# design.net
KiCad netlist of a schematic drawn in Altium Designer
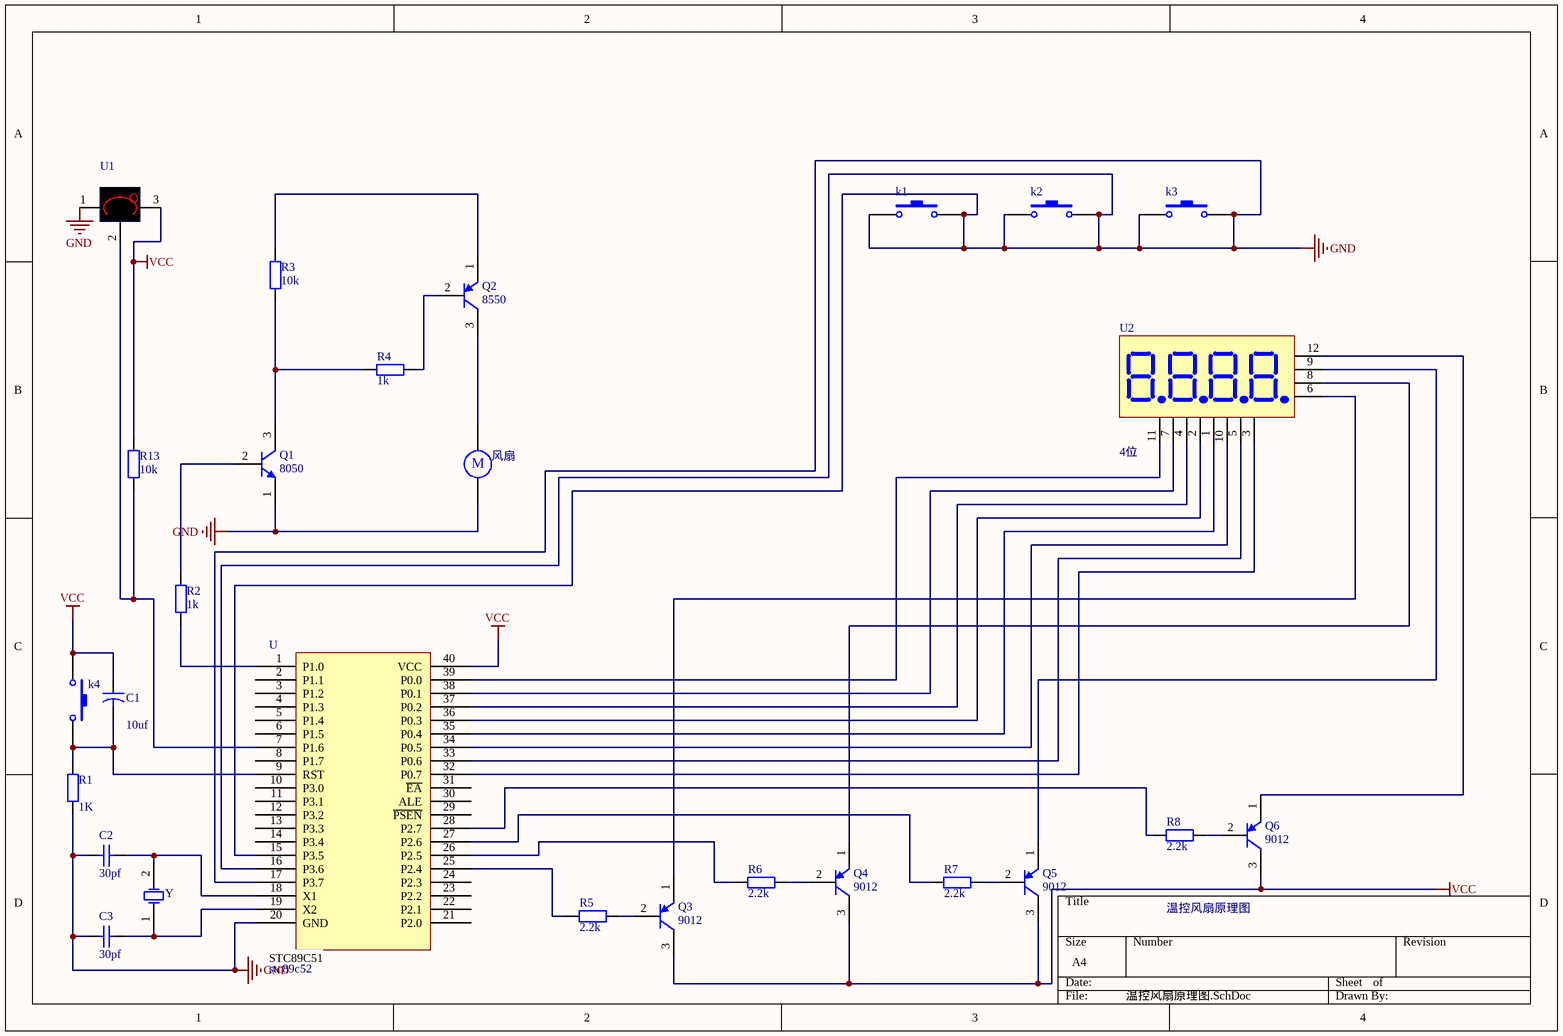
[diagram p0: 温控风扇原理图.SchDoc]

(export (version "E")
  (design (tool "Eeschema 10.0.6"))
  (components
    (comp (ref "C1")
      (value "10uf")
      (footprint "CAPR5-4X5")
      (description "Capacitor")
      (fields (field (name "Comment") "Cap2") (field (name "PUBLISHER") "Altium Limited"))
      (libsource (lib "Miscellaneous Devices") (part "Cap2"))
    )
    (comp (ref "C2")
      (value "30pf")
      (footprint "1206_C")
      (description "1206贴片电容")
      (libsource (lib "02 Miscellaneous_Devices_ZSF_Library") (part "Cap_1206"))
    )
    (comp (ref "C3")
      (value "30pf")
      (footprint "1206_C")
      (description "1206贴片电容")
      (libsource (lib "02 Miscellaneous_Devices_ZSF_Library") (part "Cap_1206"))
    )
    (comp (ref "k1")
      (value "Tactile Switch")
      (footprint "BUTTON_6*6")
      (description "Tactile Switch触觉开关")
      (fields (field (name "PUBLISHER") "Altium Limited"))
      (libsource (lib "02 Miscellaneous_Devices_ZSF_Library") (part "SW-PB"))
    )
    (comp (ref "k2")
      (value "Tactile Switch")
      (footprint "BUTTON_6*6")
      (description "Tactile Switch触觉开关")
      (fields (field (name "PUBLISHER") "Altium Limited"))
      (libsource (lib "02 Miscellaneous_Devices_ZSF_Library") (part "SW-PB"))
    )
    (comp (ref "k3")
      (value "Tactile Switch")
      (footprint "BUTTON_6*6")
      (description "Tactile Switch触觉开关")
      (fields (field (name "PUBLISHER") "Altium Limited"))
      (libsource (lib "02 Miscellaneous_Devices_ZSF_Library") (part "SW-PB"))
    )
    (comp (ref "k4")
      (value "Tactile Switch")
      (footprint "BUTTON_6*6")
      (description "Tactile Switch触觉开关")
      (fields (field (name "PUBLISHER") "Altium Limited"))
      (libsource (lib "02 Miscellaneous_Devices_ZSF_Library") (part "SW-PB"))
    )
    (comp (ref "Q1")
      (value "8050")
      (footprint "TO-92(TO-92-3)")
      (description "NPN型小功率三极管")
      (libsource (lib "02 Miscellaneous_Devices_ZSF_Library") (part "8050_TO-92"))
    )
    (comp (ref "Q2")
      (value "8550")
      (footprint "TO-92(TO-92-3)")
      (description "PNP型小功率三极管")
      (libsource (lib "02 Miscellaneous_Devices_ZSF_Library") (part "8550_TO-92"))
    )
    (comp (ref "Q3")
      (value "9012")
      (footprint "TO-92(TO-92-3)")
      (description "PNP型小功率三极管")
      (libsource (lib "02 Miscellaneous_Devices_ZSF_Library") (part "9012_TO-92"))
    )
    (comp (ref "Q4")
      (value "9012")
      (footprint "TO-92(TO-92-3)")
      (description "PNP型小功率三极管")
      (libsource (lib "02 Miscellaneous_Devices_ZSF_Library") (part "9012_TO-92"))
    )
    (comp (ref "Q5")
      (value "9012")
      (footprint "TO-92(TO-92-3)")
      (description "PNP型小功率三极管")
      (libsource (lib "02 Miscellaneous_Devices_ZSF_Library") (part "9012_TO-92"))
    )
    (comp (ref "Q6")
      (value "9012")
      (footprint "TO-92(TO-92-3)")
      (description "PNP型小功率三极管")
      (libsource (lib "02 Miscellaneous_Devices_ZSF_Library") (part "9012_TO-92"))
    )
    (comp (ref "R1")
      (value "1K")
      (footprint "AXIAL-0.4")
      (description "Resistor")
      (fields (field (name "Comment") "Res2") (field (name "PUBLISHER") "Altium Limited"))
      (libsource (lib "Miscellaneous Devices") (part "Res2"))
    )
    (comp (ref "R2")
      (value "1k")
      (footprint "AXIAL-0.6-R")
      (description "Resistor 直插电阻 1W")
      (fields (field (name "PUBLISHER") "Altium Limited"))
      (libsource (lib "02 Miscellaneous_Devices_ZSF_Library") (part "Res2_1W"))
    )
    (comp (ref "R3")
      (value "10k")
      (footprint "AXIAL-0.6-R")
      (description "Resistor 直插电阻 1W")
      (fields (field (name "PUBLISHER") "Altium Limited"))
      (libsource (lib "02 Miscellaneous_Devices_ZSF_Library") (part "Res2_1W"))
    )
    (comp (ref "R4")
      (value "1k")
      (footprint "AXIAL-0.6-R")
      (description "Resistor 直插电阻 1W")
      (fields (field (name "PUBLISHER") "Altium Limited"))
      (libsource (lib "") (part "Res2_1W_1"))
    )
    (comp (ref "R5")
      (value "2.2k")
      (footprint "AXIAL-0.8-R")
      (description "Resistor 直插电阻 2W")
      (fields (field (name "PUBLISHER") "Altium Limited"))
      (libsource (lib "02 Miscellaneous_Devices_ZSF_Library") (part "Res2_2W"))
    )
    (comp (ref "R6")
      (value "2.2k")
      (footprint "AXIAL-0.8-R")
      (description "Resistor 直插电阻 2W")
      (fields (field (name "PUBLISHER") "Altium Limited"))
      (libsource (lib "02 Miscellaneous_Devices_ZSF_Library") (part "Res2_2W"))
    )
    (comp (ref "R7")
      (value "2.2k")
      (footprint "AXIAL-0.8-R")
      (description "Resistor 直插电阻 2W")
      (fields (field (name "PUBLISHER") "Altium Limited"))
      (libsource (lib "02 Miscellaneous_Devices_ZSF_Library") (part "Res2_2W"))
    )
    (comp (ref "R8")
      (value "2.2k")
      (footprint "AXIAL-0.8-R")
      (description "Resistor 直插电阻 2W")
      (fields (field (name "PUBLISHER") "Altium Limited"))
      (libsource (lib "02 Miscellaneous_Devices_ZSF_Library") (part "Res2_2W"))
    )
    (comp (ref "R13")
      (value "10k")
      (footprint "AXIAL-0.6-R")
      (description "Resistor 直插电阻 1W")
      (fields (field (name "PUBLISHER") "Altium Limited"))
      (libsource (lib "02 Miscellaneous_Devices_ZSF_Library") (part "Res2_1W"))
    )
    (comp (ref "U")
      (value "stc89c52")
      (footprint "stc89c52:stc89c52")
      (libsource (lib "stc89c52") (part "stc89c52"))
    )
    (comp (ref "U1")
      (value "DSB18B20")
      (footprint "BCY-W3/E4")
      (description "Temperature Sensor")
      (libsource (lib "03-EButterflyIntegratedLibrary") (part "DSB18B20"))
    )
    (comp (ref "U2")
      (value "4位")
      (footprint "SEG4_3641")
      (description "4位一体共阳数码管 0.36英寸30mm*14mm*7.2mm")
      (libsource (lib "02 Miscellaneous_Devices_ZSF_Library") (part "4位-共阳"))
    )
    (comp (ref "Y")
      (value "XTAL")
      (footprint "R38")
      (description "Crystal Oscillator")
      (fields (field (name "PUBLISHER") "Altium Limited"))
      (libsource (lib "Miscellaneous Devices") (part "XTAL"))
    )
    (comp (ref "风扇")
      (value "Motor")
      (footprint "RB5-10.5")
      (description "Motor, General Kind")
      (fields (field (name "PUBLISHER") "Altium Limited"))
      (libsource (lib "Miscellaneous Devices") (part "Motor"))
    )
  )
  (nets
    (net (code "1") (name "GND") (class "Default")
      (node (ref "C2") (pin "1") (pinfunction "1_1") (pintype "passive"))
      (node (ref "C3") (pin "1") (pinfunction "1_1") (pintype "passive"))
      (node (ref "Q1") (pin "1") (pinfunction "E_1") (pintype "passive"))
      (node (ref "R1") (pin "1") (pinfunction "1_1") (pintype "passive"))
      (node (ref "U") (pin "15") (pinfunction "P3.5_15") (pintype "passive"))
      (node (ref "U") (pin "16") (pinfunction "P3.6_16") (pintype "passive"))
      (node (ref "U") (pin "17") (pinfunction "P3.7_17") (pintype "passive"))
      (node (ref "U") (pin "20") (pinfunction "GND_20") (pintype "passive"))
      (node (ref "U1") (pin "1") (pinfunction "GND_1") (pintype "passive"))
      (node (ref "k1") (pin "1") (pinfunction "1_1") (pintype "passive"))
      (node (ref "k1") (pin "2") (pinfunction "2_2") (pintype "passive"))
      (node (ref "k2") (pin "1") (pinfunction "1_1") (pintype "passive"))
      (node (ref "k2") (pin "2") (pinfunction "2_2") (pintype "passive"))
      (node (ref "k3") (pin "1") (pinfunction "1_1") (pintype "passive"))
      (node (ref "k3") (pin "2") (pinfunction "2_2") (pintype "passive"))
      (node (ref "风扇") (pin "2") (pinfunction "2_2") (pintype "passive"))
    )
    (net (code "2") (name "Net-(Q1-B)") (class "Default")
      (node (ref "Q1") (pin "2") (pinfunction "B_2") (pintype "passive"))
      (node (ref "R2") (pin "2") (pinfunction "2_2") (pintype "passive"))
    )
    (net (code "3") (name "Net-(Q1-C)") (class "Default")
      (node (ref "Q1") (pin "3") (pinfunction "C_3") (pintype "passive"))
      (node (ref "R3") (pin "1") (pinfunction "1_1") (pintype "passive"))
      (node (ref "R4") (pin "1") (pinfunction "1_1") (pintype "passive"))
    )
    (net (code "4") (name "Net-(Q2-B)") (class "Default")
      (node (ref "Q2") (pin "2") (pinfunction "B_2") (pintype "passive"))
      (node (ref "R4") (pin "2") (pinfunction "2_2") (pintype "passive"))
    )
    (net (code "5") (name "Net-(Q2-C)") (class "Default")
      (node (ref "Q2") (pin "3") (pinfunction "C_3") (pintype "passive"))
      (node (ref "风扇") (pin "1") (pinfunction "1_1") (pintype "passive"))
    )
    (net (code "6") (name "Net-(Q2-E)") (class "Default")
      (node (ref "Q2") (pin "1") (pinfunction "E_1") (pintype "passive"))
      (node (ref "R3") (pin "2") (pinfunction "2_2") (pintype "passive"))
    )
    (net (code "7") (name "Net-(Q3-B)") (class "Default")
      (node (ref "Q3") (pin "2") (pinfunction "B_2") (pintype "passive"))
      (node (ref "R5") (pin "2") (pinfunction "2_2") (pintype "passive"))
    )
    (net (code "8") (name "Net-(Q3-E)") (class "Default")
      (node (ref "Q3") (pin "1") (pinfunction "E_1") (pintype "passive"))
      (node (ref "U2") (pin "6") (pinfunction "h1_6") (pintype "passive"))
    )
    (net (code "9") (name "Net-(Q4-B)") (class "Default")
      (node (ref "Q4") (pin "2") (pinfunction "B_2") (pintype "passive"))
      (node (ref "R6") (pin "2") (pinfunction "2_2") (pintype "passive"))
    )
    (net (code "10") (name "Net-(Q4-E)") (class "Default")
      (node (ref "Q4") (pin "1") (pinfunction "E_1") (pintype "passive"))
      (node (ref "U2") (pin "8") (pinfunction "h2_8") (pintype "passive"))
    )
    (net (code "11") (name "Net-(Q5-B)") (class "Default")
      (node (ref "Q5") (pin "2") (pinfunction "B_2") (pintype "passive"))
      (node (ref "R7") (pin "2") (pinfunction "2_2") (pintype "passive"))
    )
    (net (code "12") (name "Net-(Q5-E)") (class "Default")
      (node (ref "Q5") (pin "1") (pinfunction "E_1") (pintype "passive"))
      (node (ref "U2") (pin "9") (pinfunction "h3_9") (pintype "passive"))
    )
    (net (code "13") (name "Net-(Q6-B)") (class "Default")
      (node (ref "Q6") (pin "2") (pinfunction "B_2") (pintype "passive"))
      (node (ref "R8") (pin "2") (pinfunction "2_2") (pintype "passive"))
    )
    (net (code "14") (name "Net-(Q6-E)") (class "Default")
      (node (ref "Q6") (pin "1") (pinfunction "E_1") (pintype "passive"))
      (node (ref "U2") (pin "12") (pinfunction "h4_12") (pintype "passive"))
    )
    (net (code "15") (name "Net-(U-P0.0)") (class "Default")
      (node (ref "U") (pin "39") (pinfunction "P0.0_39") (pintype "passive"))
      (node (ref "U2") (pin "11") (pinfunction "a_11") (pintype "passive"))
    )
    (net (code "16") (name "Net-(U-P0.1)") (class "Default")
      (node (ref "U") (pin "38") (pinfunction "P0.1_38") (pintype "passive"))
      (node (ref "U2") (pin "7") (pinfunction "b_7") (pintype "passive"))
    )
    (net (code "17") (name "Net-(U-P0.2)") (class "Default")
      (node (ref "U") (pin "37") (pinfunction "P0.2_37") (pintype "passive"))
      (node (ref "U2") (pin "4") (pinfunction "c_4") (pintype "passive"))
    )
    (net (code "18") (name "Net-(U-P0.3)") (class "Default")
      (node (ref "U") (pin "36") (pinfunction "P0.3_36") (pintype "passive"))
      (node (ref "U2") (pin "2") (pinfunction "d_2") (pintype "passive"))
    )
    (net (code "19") (name "Net-(U-P0.4)") (class "Default")
      (node (ref "U") (pin "35") (pinfunction "P0.4_35") (pintype "passive"))
      (node (ref "U2") (pin "1") (pinfunction "e_1") (pintype "passive"))
    )
    (net (code "20") (name "Net-(U-P0.5)") (class "Default")
      (node (ref "U") (pin "34") (pinfunction "P0.5_34") (pintype "passive"))
      (node (ref "U2") (pin "10") (pinfunction "f_10") (pintype "passive"))
    )
    (net (code "21") (name "Net-(U-P0.6)") (class "Default")
      (node (ref "U") (pin "33") (pinfunction "P0.6_33") (pintype "passive"))
      (node (ref "U2") (pin "5") (pinfunction "g_5") (pintype "passive"))
    )
    (net (code "22") (name "Net-(U-P0.7)") (class "Default")
      (node (ref "U") (pin "32") (pinfunction "P0.7_32") (pintype "passive"))
      (node (ref "U2") (pin "3") (pinfunction "dp_3") (pintype "passive"))
    )
    (net (code "23") (name "Net-(U-P1.0)") (class "Default")
      (node (ref "R2") (pin "1") (pinfunction "1_1") (pintype "passive"))
      (node (ref "U") (pin "1") (pinfunction "P1.0_1") (pintype "passive"))
    )
    (net (code "24") (name "Net-(U-P1.6)") (class "Default")
      (node (ref "R13") (pin "1") (pinfunction "1_1") (pintype "passive"))
      (node (ref "U") (pin "7") (pinfunction "P1.6_7") (pintype "passive"))
      (node (ref "U1") (pin "2") (pinfunction "DATA_2") (pintype "passive"))
    )
    (net (code "25") (name "Net-(U-P2.4)") (class "Default")
      (node (ref "R5") (pin "1") (pinfunction "1_1") (pintype "passive"))
      (node (ref "U") (pin "25") (pinfunction "P2.4_25") (pintype "passive"))
    )
    (net (code "26") (name "Net-(U-P2.5)") (class "Default")
      (node (ref "R6") (pin "1") (pinfunction "1_1") (pintype "passive"))
      (node (ref "U") (pin "26") (pinfunction "P2.5_26") (pintype "passive"))
    )
    (net (code "27") (name "Net-(U-P2.6)") (class "Default")
      (node (ref "R7") (pin "1") (pinfunction "1_1") (pintype "passive"))
      (node (ref "U") (pin "27") (pinfunction "P2.6_27") (pintype "passive"))
    )
    (net (code "28") (name "Net-(U-P2.7)") (class "Default")
      (node (ref "R8") (pin "1") (pinfunction "1_1") (pintype "passive"))
      (node (ref "U") (pin "28") (pinfunction "P2.7_28") (pintype "passive"))
    )
    (net (code "29") (name "Net-(U-RST)") (class "Default")
      (node (ref "C1") (pin "2") (pinfunction "2_2") (pintype "passive"))
      (node (ref "R1") (pin "2") (pinfunction "2_2") (pintype "passive"))
      (node (ref "U") (pin "9") (pinfunction "RST_9") (pintype "passive"))
      (node (ref "k4") (pin "2") (pinfunction "2_2") (pintype "passive"))
    )
    (net (code "30") (name "Net-(U-X1)") (class "Default")
      (node (ref "C2") (pin "2") (pinfunction "2_2") (pintype "passive"))
      (node (ref "U") (pin "18") (pinfunction "X1_18") (pintype "passive"))
      (node (ref "Y") (pin "2") (pinfunction "OSC2_2") (pintype "passive"))
    )
    (net (code "31") (name "Net-(U-X2)") (class "Default")
      (node (ref "C3") (pin "2") (pinfunction "2_2") (pintype "passive"))
      (node (ref "U") (pin "19") (pinfunction "X2_19") (pintype "passive"))
      (node (ref "Y") (pin "1") (pinfunction "OSC1_1") (pintype "passive"))
    )
    (net (code "32") (name "VCC") (class "Default")
      (node (ref "C1") (pin "1") (pinfunction "1_1") (pintype "passive"))
      (node (ref "Q3") (pin "3") (pinfunction "C_3") (pintype "passive"))
      (node (ref "Q4") (pin "3") (pinfunction "C_3") (pintype "passive"))
      (node (ref "Q5") (pin "3") (pinfunction "C_3") (pintype "passive"))
      (node (ref "Q6") (pin "3") (pinfunction "C_3") (pintype "passive"))
      (node (ref "R13") (pin "2") (pinfunction "2_2") (pintype "passive"))
      (node (ref "U") (pin "40") (pinfunction "VCC_40") (pintype "passive"))
      (node (ref "U1") (pin "3") (pinfunction "VDD_3") (pintype "passive"))
      (node (ref "k4") (pin "1") (pinfunction "1_1") (pintype "passive"))
    )
    (net (code "33") (name "unconnected-(U-ALE-Pad30)") (class "Default")
      (node (ref "U") (pin "30") (pinfunction "ALE_30") (pintype "passive"))
    )
    (net (code "34") (name "unconnected-(U-P1.1-Pad2)") (class "Default")
      (node (ref "U") (pin "2") (pinfunction "P1.1_2") (pintype "passive"))
    )
    (net (code "35") (name "unconnected-(U-P1.2-Pad3)") (class "Default")
      (node (ref "U") (pin "3") (pinfunction "P1.2_3") (pintype "passive"))
    )
    (net (code "36") (name "unconnected-(U-P1.3-Pad4)") (class "Default")
      (node (ref "U") (pin "4") (pinfunction "P1.3_4") (pintype "passive"))
    )
    (net (code "37") (name "unconnected-(U-P1.4-Pad5)") (class "Default")
      (node (ref "U") (pin "5") (pinfunction "P1.4_5") (pintype "passive"))
    )
    (net (code "38") (name "unconnected-(U-P1.5-Pad6)") (class "Default")
      (node (ref "U") (pin "6") (pinfunction "P1.5_6") (pintype "passive"))
    )
    (net (code "39") (name "unconnected-(U-P1.7-Pad8)") (class "Default")
      (node (ref "U") (pin "8") (pinfunction "P1.7_8") (pintype "passive"))
    )
    (net (code "40") (name "unconnected-(U-P2.0-Pad21)") (class "Default")
      (node (ref "U") (pin "21") (pinfunction "P2.0_21") (pintype "passive"))
    )
    (net (code "41") (name "unconnected-(U-P2.1-Pad22)") (class "Default")
      (node (ref "U") (pin "22") (pinfunction "P2.1_22") (pintype "passive"))
    )
    (net (code "42") (name "unconnected-(U-P2.2-Pad23)") (class "Default")
      (node (ref "U") (pin "23") (pinfunction "P2.2_23") (pintype "passive"))
    )
    (net (code "43") (name "unconnected-(U-P2.3-Pad24)") (class "Default")
      (node (ref "U") (pin "24") (pinfunction "P2.3_24") (pintype "passive"))
    )
    (net (code "44") (name "unconnected-(U-P3.0-Pad10)") (class "Default")
      (node (ref "U") (pin "10") (pinfunction "P3.0_10") (pintype "passive"))
    )
    (net (code "45") (name "unconnected-(U-P3.1-Pad11)") (class "Default")
      (node (ref "U") (pin "11") (pinfunction "P3.1_11") (pintype "passive"))
    )
    (net (code "46") (name "unconnected-(U-P3.2-Pad12)") (class "Default")
      (node (ref "U") (pin "12") (pinfunction "P3.2_12") (pintype "passive"))
    )
    (net (code "47") (name "unconnected-(U-P3.3-Pad13)") (class "Default")
      (node (ref "U") (pin "13") (pinfunction "P3.3_13") (pintype "passive"))
    )
    (net (code "48") (name "unconnected-(U-P3.4-Pad14)") (class "Default")
      (node (ref "U") (pin "14") (pinfunction "P3.4_14") (pintype "passive"))
    )
    (net (code "49") (name "unconnected-(U-~{EA}-Pad31)") (class "Default")
      (node (ref "U") (pin "31") (pinfunction "~{EA}_31") (pintype "passive"))
    )
    (net (code "50") (name "unconnected-(U-~{PSEN}-Pad29)") (class "Default")
      (node (ref "U") (pin "29") (pinfunction "~{PSEN}_29") (pintype "passive"))
    )
  )
)
